# transmitter.net
KiCad netlist of a schematic drawn in EAGLE
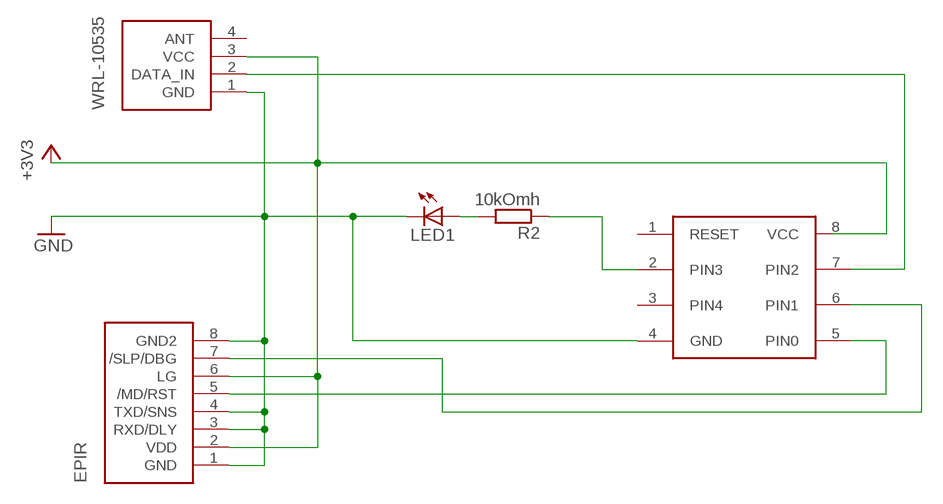
[diagram p0: schematic, sheet 1]

(export (version "E")
  (design (tool "Eeschema 10.0.6"))
  (components
    (comp (ref "LED1")
      (value "LED")
      (footprint "eagle-import:SMARTLED-TTW")
      (libsource (lib "eagle-import") (part "LED"))
    )
    (comp (ref "R2")
      (value "10kOmh")
      (footprint "eagle-import:0204V")
      (libsource (lib "eagle-import") (part "R-EU_0204/2V"))
    )
    (comp (ref "U$1")
      (value "EPIR")
      (footprint "eagle-import:EPIR")
      (libsource (lib "eagle-import") (part "EPIR"))
    )
    (comp (ref "U$2")
      (value "WRL-10535")
      (footprint "eagle-import:WRL-10535")
      (libsource (lib "eagle-import") (part "WRL-10535"))
    )
    (comp (ref "U$3")
      (value "ATTINY85")
      (footprint "eagle-import:ATTINY85")
      (libsource (lib "eagle-import") (part "ATTINY85"))
    )
  )
  (nets
    (net (code "1") (name "+3V3") (class "Default")
      (node (ref "U$1") (pin "2") (pinfunction "VDD_2") (pintype "bidirectional"))
      (node (ref "U$1") (pin "6") (pinfunction "LG_6") (pintype "bidirectional"))
      (node (ref "U$2") (pin "3") (pinfunction "VCC_3") (pintype "bidirectional"))
    )
    (net (code "2") (name "GND") (class "Default")
      (node (ref "LED1") (pin "C@1") (pinfunction "C_C@1") (pintype "passive"))
      (node (ref "U$1") (pin "1") (pinfunction "GND_1") (pintype "bidirectional"))
      (node (ref "U$1") (pin "3") (pinfunction "RXD/DLY_3") (pintype "bidirectional"))
      (node (ref "U$1") (pin "4") (pinfunction "TXD/SNS_4") (pintype "bidirectional"))
      (node (ref "U$1") (pin "8") (pinfunction "GND2_8") (pintype "bidirectional"))
      (node (ref "U$2") (pin "1") (pinfunction "GND_1") (pintype "bidirectional"))
      (node (ref "U$3") (pin "4") (pinfunction "GND_4") (pintype "bidirectional"))
    )
    (net (code "3") (name "Net-(LED1-A)") (class "Default")
      (node (ref "LED1") (pin "A@1") (pinfunction "A_A@1") (pintype "passive"))
      (node (ref "R2") (pin "2") (pinfunction "2_2") (pintype "passive"))
    )
    (net (code "4") (name "Net-(U$1-{slash}MD{slash}RST)") (class "Default")
      (node (ref "U$1") (pin "5") (pinfunction "/MD/RST_5") (pintype "bidirectional"))
      (node (ref "U$3") (pin "5") (pinfunction "PIN0_5") (pintype "bidirectional"))
    )
    (net (code "5") (name "Net-(U$1-{slash}SLP{slash}DBG)") (class "Default")
      (node (ref "U$1") (pin "7") (pinfunction "/SLP/DBG_7") (pintype "bidirectional"))
      (node (ref "U$3") (pin "6") (pinfunction "PIN1_6") (pintype "bidirectional"))
    )
    (net (code "6") (name "Net-(U$2-DATA_IN)") (class "Default")
      (node (ref "U$2") (pin "2") (pinfunction "DATA_IN_2") (pintype "bidirectional"))
      (node (ref "U$3") (pin "7") (pinfunction "PIN2_7") (pintype "bidirectional"))
    )
    (net (code "7") (name "Net-(U$3-PIN3)") (class "Default")
      (node (ref "R2") (pin "1") (pinfunction "1_1") (pintype "passive"))
      (node (ref "U$3") (pin "2") (pinfunction "PIN3_2") (pintype "bidirectional"))
    )
    (net (code "8") (name "unconnected-(U$2-ANT-Pad4)") (class "Default")
      (node (ref "U$2") (pin "4") (pinfunction "ANT_4") (pintype "bidirectional"))
    )
    (net (code "9") (name "unconnected-(U$3-PIN4-Pad3)") (class "Default")
      (node (ref "U$3") (pin "3") (pinfunction "PIN4_3") (pintype "bidirectional"))
    )
    (net (code "10") (name "unconnected-(U$3-RESET-Pad1)") (class "Default")
      (node (ref "U$3") (pin "1") (pinfunction "RESET_1") (pintype "bidirectional"))
    )
    (net (code "11") (name "unconnected-(U$3-VCC-Pad8)") (class "Default")
      (node (ref "U$3") (pin "8") (pinfunction "VCC_8") (pintype "bidirectional"))
    )
  )
)
